# Sheet1.net
KiCad netlist of a schematic drawn in Altium Designer
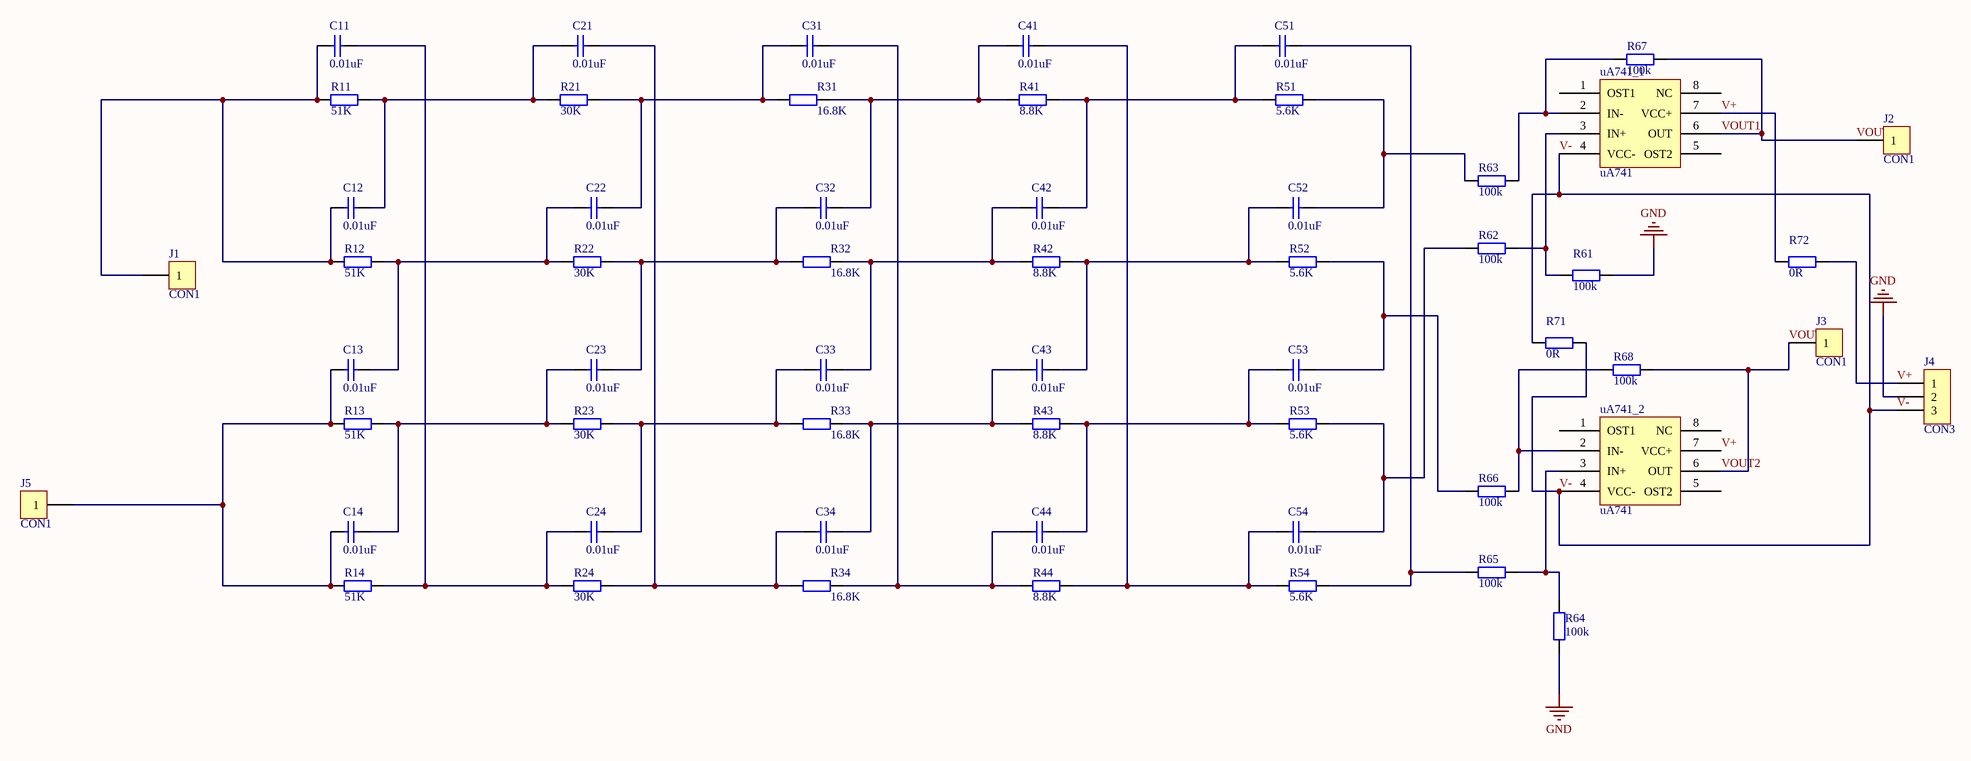
[diagram p0: Sheet1.SchDoc]

(export (version "E")
  (design (tool "Eeschema 10.0.6"))
  (components
    (comp (ref "C11")
      (value "0.01uF")
      (footprint "0603C")
      (description "Capacitor")
      (fields (field (name "PUBLISHER") "Altium Limited"))
      (libsource (lib "TH-SMT_WT_MP 1.0") (part "Cap"))
    )
    (comp (ref "C12")
      (value "0.01uF")
      (footprint "0603C")
      (description "Capacitor")
      (fields (field (name "PUBLISHER") "Altium Limited"))
      (libsource (lib "TH-SMT_WT_MP 1.0") (part "Cap"))
    )
    (comp (ref "C13")
      (value "0.01uF")
      (footprint "0603C")
      (description "Capacitor")
      (fields (field (name "PUBLISHER") "Altium Limited"))
      (libsource (lib "TH-SMT_WT_MP 1.0") (part "Cap"))
    )
    (comp (ref "C14")
      (value "0.01uF")
      (footprint "0603C")
      (description "Capacitor")
      (fields (field (name "PUBLISHER") "Altium Limited"))
      (libsource (lib "TH-SMT_WT_MP 1.0") (part "Cap"))
    )
    (comp (ref "C21")
      (value "0.01uF")
      (footprint "0603C")
      (description "Capacitor")
      (fields (field (name "PUBLISHER") "Altium Limited"))
      (libsource (lib "TH-SMT_WT_MP 1.0") (part "Cap"))
    )
    (comp (ref "C22")
      (value "0.01uF")
      (footprint "0603C")
      (description "Capacitor")
      (fields (field (name "PUBLISHER") "Altium Limited"))
      (libsource (lib "TH-SMT_WT_MP 1.0") (part "Cap"))
    )
    (comp (ref "C23")
      (value "0.01uF")
      (footprint "0603C")
      (description "Capacitor")
      (fields (field (name "PUBLISHER") "Altium Limited"))
      (libsource (lib "TH-SMT_WT_MP 1.0") (part "Cap"))
    )
    (comp (ref "C24")
      (value "0.01uF")
      (footprint "0603C")
      (description "Capacitor")
      (fields (field (name "PUBLISHER") "Altium Limited"))
      (libsource (lib "TH-SMT_WT_MP 1.0") (part "Cap"))
    )
    (comp (ref "C31")
      (value "0.01uF")
      (footprint "0603C")
      (description "Capacitor")
      (fields (field (name "PUBLISHER") "Altium Limited"))
      (libsource (lib "TH-SMT_WT_MP 1.0") (part "Cap"))
    )
    (comp (ref "C32")
      (value "0.01uF")
      (footprint "0603C")
      (description "Capacitor")
      (fields (field (name "PUBLISHER") "Altium Limited"))
      (libsource (lib "TH-SMT_WT_MP 1.0") (part "Cap"))
    )
    (comp (ref "C33")
      (value "0.01uF")
      (footprint "0603C")
      (description "Capacitor")
      (fields (field (name "PUBLISHER") "Altium Limited"))
      (libsource (lib "TH-SMT_WT_MP 1.0") (part "Cap"))
    )
    (comp (ref "C34")
      (value "0.01uF")
      (footprint "0603C")
      (description "Capacitor")
      (fields (field (name "PUBLISHER") "Altium Limited"))
      (libsource (lib "TH-SMT_WT_MP 1.0") (part "Cap"))
    )
    (comp (ref "C41")
      (value "0.01uF")
      (footprint "0603C")
      (description "Capacitor")
      (fields (field (name "PUBLISHER") "Altium Limited"))
      (libsource (lib "TH-SMT_WT_MP 1.0") (part "Cap"))
    )
    (comp (ref "C42")
      (value "0.01uF")
      (footprint "0603C")
      (description "Capacitor")
      (fields (field (name "PUBLISHER") "Altium Limited"))
      (libsource (lib "TH-SMT_WT_MP 1.0") (part "Cap"))
    )
    (comp (ref "C43")
      (value "0.01uF")
      (footprint "0603C")
      (description "Capacitor")
      (fields (field (name "PUBLISHER") "Altium Limited"))
      (libsource (lib "TH-SMT_WT_MP 1.0") (part "Cap"))
    )
    (comp (ref "C44")
      (value "0.01uF")
      (footprint "0603C")
      (description "Capacitor")
      (fields (field (name "PUBLISHER") "Altium Limited"))
      (libsource (lib "TH-SMT_WT_MP 1.0") (part "Cap"))
    )
    (comp (ref "C51")
      (value "0.01uF")
      (footprint "0603C")
      (description "Capacitor")
      (fields (field (name "PUBLISHER") "Altium Limited"))
      (libsource (lib "TH-SMT_WT_MP 1.0") (part "Cap"))
    )
    (comp (ref "C52")
      (value "0.01uF")
      (footprint "0603C")
      (description "Capacitor")
      (fields (field (name "PUBLISHER") "Altium Limited"))
      (libsource (lib "TH-SMT_WT_MP 1.0") (part "Cap"))
    )
    (comp (ref "C53")
      (value "0.01uF")
      (footprint "0603C")
      (description "Capacitor")
      (fields (field (name "PUBLISHER") "Altium Limited"))
      (libsource (lib "TH-SMT_WT_MP 1.0") (part "Cap"))
    )
    (comp (ref "C54")
      (value "0.01uF")
      (footprint "0603C")
      (description "Capacitor")
      (fields (field (name "PUBLISHER") "Altium Limited"))
      (libsource (lib "TH-SMT_WT_MP 1.0") (part "Cap"))
    )
    (comp (ref "J1") (value "CON1") (footprint "PIN-1-1.0") (libsource (lib "常用元件库") (part "CON1")))
    (comp (ref "J2") (value "CON1") (footprint "PIN-1-1.0") (libsource (lib "常用元件库") (part "CON1")))
    (comp (ref "J3") (value "CON1") (footprint "PIN-1-1.0") (libsource (lib "常用元件库") (part "CON1")))
    (comp (ref "J4") (value "CON3") (footprint "PIN-3-2.54-1.0") (libsource (lib "常用元件库") (part "CON3")))
    (comp (ref "J5") (value "CON1") (footprint "PIN-1-1.0") (libsource (lib "") (part "CON1_1")))
    (comp (ref "R11")
      (value "51K")
      (footprint "0603R")
      (description "Resistor")
      (fields (field (name "PUBLISHER") "Altium Limited"))
      (libsource (lib "") (part "Res2_1"))
    )
    (comp (ref "R12")
      (value "51K")
      (footprint "0603R")
      (description "Resistor")
      (fields (field (name "PUBLISHER") "Altium Limited"))
      (libsource (lib "") (part "Res2_1"))
    )
    (comp (ref "R13")
      (value "51K")
      (footprint "0603R")
      (description "Resistor")
      (fields (field (name "PUBLISHER") "Altium Limited"))
      (libsource (lib "") (part "Res2_1"))
    )
    (comp (ref "R14")
      (value "51K")
      (footprint "0603R")
      (description "Resistor")
      (fields (field (name "PUBLISHER") "Altium Limited"))
      (libsource (lib "") (part "Res2_1"))
    )
    (comp (ref "R21")
      (value "30K")
      (footprint "0603R")
      (description "Resistor")
      (fields (field (name "PUBLISHER") "Altium Limited"))
      (libsource (lib "") (part "Res2_1"))
    )
    (comp (ref "R22")
      (value "30K")
      (footprint "0603R")
      (description "Resistor")
      (fields (field (name "PUBLISHER") "Altium Limited"))
      (libsource (lib "") (part "Res2_1"))
    )
    (comp (ref "R23")
      (value "30K")
      (footprint "0603R")
      (description "Resistor")
      (fields (field (name "PUBLISHER") "Altium Limited"))
      (libsource (lib "") (part "Res2_1"))
    )
    (comp (ref "R24")
      (value "30K")
      (footprint "0603R")
      (description "Resistor")
      (fields (field (name "PUBLISHER") "Altium Limited"))
      (libsource (lib "") (part "Res2_1"))
    )
    (comp (ref "R31")
      (value "16.8K")
      (footprint "0603R")
      (description "Resistor")
      (fields (field (name "PUBLISHER") "Altium Limited"))
      (libsource (lib "") (part "Res2_1"))
    )
    (comp (ref "R32")
      (value "16.8K")
      (footprint "0603R")
      (description "Resistor")
      (fields (field (name "PUBLISHER") "Altium Limited"))
      (libsource (lib "") (part "Res2_1"))
    )
    (comp (ref "R33")
      (value "16.8K")
      (footprint "0603R")
      (description "Resistor")
      (fields (field (name "PUBLISHER") "Altium Limited"))
      (libsource (lib "") (part "Res2_1"))
    )
    (comp (ref "R34")
      (value "16.8K")
      (footprint "0603R")
      (description "Resistor")
      (fields (field (name "PUBLISHER") "Altium Limited"))
      (libsource (lib "") (part "Res2_1"))
    )
    (comp (ref "R41")
      (value "8.8K")
      (footprint "0603R")
      (description "Resistor")
      (fields (field (name "PUBLISHER") "Altium Limited"))
      (libsource (lib "") (part "Res2_1"))
    )
    (comp (ref "R42")
      (value "8.8K")
      (footprint "0603R")
      (description "Resistor")
      (fields (field (name "PUBLISHER") "Altium Limited"))
      (libsource (lib "") (part "Res2_1"))
    )
    (comp (ref "R43")
      (value "8.8K")
      (footprint "0603R")
      (description "Resistor")
      (fields (field (name "PUBLISHER") "Altium Limited"))
      (libsource (lib "") (part "Res2_1"))
    )
    (comp (ref "R44")
      (value "8.8K")
      (footprint "0603R")
      (description "Resistor")
      (fields (field (name "PUBLISHER") "Altium Limited"))
      (libsource (lib "") (part "Res2_1"))
    )
    (comp (ref "R51")
      (value "5.6K")
      (footprint "0603R")
      (description "Resistor")
      (fields (field (name "PUBLISHER") "Altium Limited"))
      (libsource (lib "TH-SMT_WT_MP 1.0") (part "Res2"))
    )
    (comp (ref "R52")
      (value "5.6K")
      (footprint "0603R")
      (description "Resistor")
      (fields (field (name "PUBLISHER") "Altium Limited"))
      (libsource (lib "TH-SMT_WT_MP 1.0") (part "Res2"))
    )
    (comp (ref "R53")
      (value "5.6K")
      (footprint "0603R")
      (description "Resistor")
      (fields (field (name "PUBLISHER") "Altium Limited"))
      (libsource (lib "TH-SMT_WT_MP 1.0") (part "Res2"))
    )
    (comp (ref "R54")
      (value "5.6K")
      (footprint "0603R")
      (description "Resistor")
      (fields (field (name "PUBLISHER") "Altium Limited"))
      (libsource (lib "TH-SMT_WT_MP 1.0") (part "Res2"))
    )
    (comp (ref "R61")
      (value "100k")
      (footprint "0603R")
      (description "Resistor")
      (libsource (lib "") (part "RES_1"))
    )
    (comp (ref "R62")
      (value "100k")
      (footprint "Inductor2")
      (description "Resistor")
      (libsource (lib "General") (part "RES"))
    )
    (comp (ref "R63")
      (value "100k")
      (footprint "0603R")
      (description "Resistor")
      (libsource (lib "General") (part "RES"))
    )
    (comp (ref "R64")
      (value "100k")
      (footprint "0603R")
      (description "Resistor")
      (libsource (lib "") (part "RES_2"))
    )
    (comp (ref "R65")
      (value "100k")
      (footprint "0603R")
      (description "Resistor")
      (libsource (lib "General") (part "RES"))
    )
    (comp (ref "R66")
      (value "100k")
      (footprint "Inductor2")
      (description "Resistor")
      (libsource (lib "General") (part "RES"))
    )
    (comp (ref "R67")
      (value "100k")
      (footprint "0603R")
      (description "Resistor")
      (libsource (lib "General") (part "RES"))
    )
    (comp (ref "R68")
      (value "100k")
      (footprint "0603R")
      (description "Resistor")
      (libsource (lib "General") (part "RES"))
    )
    (comp (ref "R71")
      (value "0R")
      (footprint "Inductor2")
      (description "Resistor")
      (libsource (lib "") (part "RES_1"))
    )
    (comp (ref "R72")
      (value "0R")
      (footprint "Inductor2")
      (description "Resistor")
      (libsource (lib "") (part "RES_1"))
    )
    (comp (ref "uA741_1") (value "uA741") (footprint "DIP-8") (libsource (lib "General") (part "uA741")))
    (comp (ref "uA741_2") (value "uA741") (footprint "DIP-8") (libsource (lib "General") (part "uA741")))
  )
  (nets
    (net (code "1") (name "/V+") (class "Default")
      (node (ref "J4") (pin "1") (pinfunction "1_1") (pintype "passive"))
      (node (ref "R72") (pin "1") (pinfunction "1_1") (pintype "passive"))
      (node (ref "R72") (pin "2") (pinfunction "2_2") (pintype "passive"))
      (node (ref "uA741_1") (pin "7") (pinfunction "VCC+_7") (pintype "passive"))
      (node (ref "uA741_2") (pin "7") (pinfunction "VCC+_7") (pintype "passive"))
    )
    (net (code "2") (name "/V-") (class "Default")
      (node (ref "J4") (pin "3") (pinfunction "3_3") (pintype "passive"))
      (node (ref "R71") (pin "1") (pinfunction "1_1") (pintype "passive"))
      (node (ref "R71") (pin "2") (pinfunction "2_2") (pintype "passive"))
      (node (ref "uA741_1") (pin "4") (pinfunction "VCC-_4") (pintype "passive"))
      (node (ref "uA741_2") (pin "4") (pinfunction "VCC-_4") (pintype "passive"))
    )
    (net (code "3") (name "/VOUT1") (class "Default")
      (node (ref "J2") (pin "1") (pinfunction "1_1") (pintype "passive"))
      (node (ref "R67") (pin "2") (pinfunction "2_2") (pintype "passive"))
      (node (ref "uA741_1") (pin "6") (pinfunction "OUT_6") (pintype "passive"))
    )
    (net (code "4") (name "/VOUT2") (class "Default")
      (node (ref "J3") (pin "1") (pinfunction "1_1") (pintype "passive"))
      (node (ref "R68") (pin "2") (pinfunction "2_2") (pintype "passive"))
      (node (ref "uA741_2") (pin "6") (pinfunction "OUT_6") (pintype "passive"))
    )
    (net (code "5") (name "GND") (class "Default")
      (node (ref "J4") (pin "2") (pinfunction "2_2") (pintype "passive"))
      (node (ref "R61") (pin "1") (pinfunction "1_1") (pintype "passive"))
      (node (ref "R64") (pin "2") (pinfunction "2_2") (pintype "passive"))
    )
    (net (code "6") (name "Net-(C11-Pad1)") (class "Default")
      (node (ref "C11") (pin "1") (pinfunction "1_1") (pintype "passive"))
      (node (ref "C12") (pin "1") (pinfunction "1_1") (pintype "passive"))
      (node (ref "J1") (pin "1") (pinfunction "1_1") (pintype "passive"))
      (node (ref "R11") (pin "1") (pinfunction "1_1") (pintype "passive"))
      (node (ref "R12") (pin "1") (pinfunction "1_1") (pintype "passive"))
    )
    (net (code "7") (name "Net-(C11-Pad2)") (class "Default")
      (node (ref "C11") (pin "2") (pinfunction "2_2") (pintype "passive"))
      (node (ref "C24") (pin "1") (pinfunction "1_1") (pintype "passive"))
      (node (ref "R14") (pin "2") (pinfunction "2_2") (pintype "passive"))
      (node (ref "R24") (pin "1") (pinfunction "1_1") (pintype "passive"))
    )
    (net (code "8") (name "Net-(C12-Pad2)") (class "Default")
      (node (ref "C12") (pin "2") (pinfunction "2_2") (pintype "passive"))
      (node (ref "C21") (pin "1") (pinfunction "1_1") (pintype "passive"))
      (node (ref "R11") (pin "2") (pinfunction "2_2") (pintype "passive"))
      (node (ref "R21") (pin "1") (pinfunction "1_1") (pintype "passive"))
    )
    (net (code "9") (name "Net-(C13-Pad1)") (class "Default")
      (node (ref "C13") (pin "1") (pinfunction "1_1") (pintype "passive"))
      (node (ref "C14") (pin "1") (pinfunction "1_1") (pintype "passive"))
      (node (ref "J5") (pin "1") (pinfunction "1_1") (pintype "passive"))
      (node (ref "R13") (pin "1") (pinfunction "1_1") (pintype "passive"))
      (node (ref "R14") (pin "1") (pinfunction "1_1") (pintype "passive"))
    )
    (net (code "10") (name "Net-(C13-Pad2)") (class "Default")
      (node (ref "C13") (pin "2") (pinfunction "2_2") (pintype "passive"))
      (node (ref "C22") (pin "1") (pinfunction "1_1") (pintype "passive"))
      (node (ref "R12") (pin "2") (pinfunction "2_2") (pintype "passive"))
      (node (ref "R22") (pin "1") (pinfunction "1_1") (pintype "passive"))
    )
    (net (code "11") (name "Net-(C14-Pad2)") (class "Default")
      (node (ref "C14") (pin "2") (pinfunction "2_2") (pintype "passive"))
      (node (ref "C23") (pin "1") (pinfunction "1_1") (pintype "passive"))
      (node (ref "R13") (pin "2") (pinfunction "2_2") (pintype "passive"))
      (node (ref "R23") (pin "1") (pinfunction "1_1") (pintype "passive"))
    )
    (net (code "12") (name "Net-(C21-Pad2)") (class "Default")
      (node (ref "C21") (pin "2") (pinfunction "2_2") (pintype "passive"))
      (node (ref "C34") (pin "1") (pinfunction "1_1") (pintype "passive"))
      (node (ref "R24") (pin "2") (pinfunction "2_2") (pintype "passive"))
      (node (ref "R34") (pin "1") (pinfunction "1_1") (pintype "passive"))
    )
    (net (code "13") (name "Net-(C22-Pad2)") (class "Default")
      (node (ref "C22") (pin "2") (pinfunction "2_2") (pintype "passive"))
      (node (ref "C31") (pin "1") (pinfunction "1_1") (pintype "passive"))
      (node (ref "R21") (pin "2") (pinfunction "2_2") (pintype "passive"))
      (node (ref "R31") (pin "1") (pinfunction "1_1") (pintype "passive"))
    )
    (net (code "14") (name "Net-(C23-Pad2)") (class "Default")
      (node (ref "C23") (pin "2") (pinfunction "2_2") (pintype "passive"))
      (node (ref "C32") (pin "1") (pinfunction "1_1") (pintype "passive"))
      (node (ref "R22") (pin "2") (pinfunction "2_2") (pintype "passive"))
      (node (ref "R32") (pin "1") (pinfunction "1_1") (pintype "passive"))
    )
    (net (code "15") (name "Net-(C24-Pad2)") (class "Default")
      (node (ref "C24") (pin "2") (pinfunction "2_2") (pintype "passive"))
      (node (ref "C33") (pin "1") (pinfunction "1_1") (pintype "passive"))
      (node (ref "R23") (pin "2") (pinfunction "2_2") (pintype "passive"))
      (node (ref "R33") (pin "1") (pinfunction "1_1") (pintype "passive"))
    )
    (net (code "16") (name "Net-(C31-Pad2)") (class "Default")
      (node (ref "C31") (pin "2") (pinfunction "2_2") (pintype "passive"))
      (node (ref "C44") (pin "1") (pinfunction "1_1") (pintype "passive"))
      (node (ref "R34") (pin "2") (pinfunction "2_2") (pintype "passive"))
      (node (ref "R44") (pin "1") (pinfunction "1_1") (pintype "passive"))
    )
    (net (code "17") (name "Net-(C32-Pad2)") (class "Default")
      (node (ref "C32") (pin "2") (pinfunction "2_2") (pintype "passive"))
      (node (ref "C41") (pin "1") (pinfunction "1_1") (pintype "passive"))
      (node (ref "R31") (pin "2") (pinfunction "2_2") (pintype "passive"))
      (node (ref "R41") (pin "1") (pinfunction "1_1") (pintype "passive"))
    )
    (net (code "18") (name "Net-(C33-Pad2)") (class "Default")
      (node (ref "C33") (pin "2") (pinfunction "2_2") (pintype "passive"))
      (node (ref "C42") (pin "1") (pinfunction "1_1") (pintype "passive"))
      (node (ref "R32") (pin "2") (pinfunction "2_2") (pintype "passive"))
      (node (ref "R42") (pin "1") (pinfunction "1_1") (pintype "passive"))
    )
    (net (code "19") (name "Net-(C34-Pad2)") (class "Default")
      (node (ref "C34") (pin "2") (pinfunction "2_2") (pintype "passive"))
      (node (ref "C43") (pin "1") (pinfunction "1_1") (pintype "passive"))
      (node (ref "R33") (pin "2") (pinfunction "2_2") (pintype "passive"))
      (node (ref "R43") (pin "1") (pinfunction "1_1") (pintype "passive"))
    )
    (net (code "20") (name "Net-(C41-Pad2)") (class "Default")
      (node (ref "C41") (pin "2") (pinfunction "2_2") (pintype "passive"))
      (node (ref "C54") (pin "1") (pinfunction "1_1") (pintype "passive"))
      (node (ref "R44") (pin "2") (pinfunction "2_2") (pintype "passive"))
      (node (ref "R54") (pin "2") (pinfunction "2_2") (pintype "passive"))
    )
    (net (code "21") (name "Net-(C42-Pad2)") (class "Default")
      (node (ref "C42") (pin "2") (pinfunction "2_2") (pintype "passive"))
      (node (ref "C51") (pin "1") (pinfunction "1_1") (pintype "passive"))
      (node (ref "R41") (pin "2") (pinfunction "2_2") (pintype "passive"))
      (node (ref "R51") (pin "2") (pinfunction "2_2") (pintype "passive"))
    )
    (net (code "22") (name "Net-(C43-Pad2)") (class "Default")
      (node (ref "C43") (pin "2") (pinfunction "2_2") (pintype "passive"))
      (node (ref "C52") (pin "1") (pinfunction "1_1") (pintype "passive"))
      (node (ref "R42") (pin "2") (pinfunction "2_2") (pintype "passive"))
      (node (ref "R52") (pin "2") (pinfunction "2_2") (pintype "passive"))
    )
    (net (code "23") (name "Net-(C44-Pad2)") (class "Default")
      (node (ref "C44") (pin "2") (pinfunction "2_2") (pintype "passive"))
      (node (ref "C53") (pin "1") (pinfunction "1_1") (pintype "passive"))
      (node (ref "R43") (pin "2") (pinfunction "2_2") (pintype "passive"))
      (node (ref "R53") (pin "2") (pinfunction "2_2") (pintype "passive"))
    )
    (net (code "24") (name "Net-(C51-Pad2)") (class "Default")
      (node (ref "C51") (pin "2") (pinfunction "2_2") (pintype "passive"))
      (node (ref "R54") (pin "1") (pinfunction "1_1") (pintype "passive"))
      (node (ref "R65") (pin "1") (pinfunction "1_1") (pintype "passive"))
    )
    (net (code "25") (name "Net-(C52-Pad2)") (class "Default")
      (node (ref "C52") (pin "2") (pinfunction "2_2") (pintype "passive"))
      (node (ref "R51") (pin "1") (pinfunction "1_1") (pintype "passive"))
      (node (ref "R63") (pin "1") (pinfunction "1_1") (pintype "passive"))
    )
    (net (code "26") (name "Net-(C53-Pad2)") (class "Default")
      (node (ref "C53") (pin "2") (pinfunction "2_2") (pintype "passive"))
      (node (ref "R52") (pin "1") (pinfunction "1_1") (pintype "passive"))
      (node (ref "R66") (pin "1") (pinfunction "1_1") (pintype "passive"))
    )
    (net (code "27") (name "Net-(C54-Pad2)") (class "Default")
      (node (ref "C54") (pin "2") (pinfunction "2_2") (pintype "passive"))
      (node (ref "R53") (pin "1") (pinfunction "1_1") (pintype "passive"))
      (node (ref "R62") (pin "1") (pinfunction "1_1") (pintype "passive"))
    )
    (net (code "28") (name "Net-(uA741_1-IN+)") (class "Default")
      (node (ref "R61") (pin "2") (pinfunction "2_2") (pintype "passive"))
      (node (ref "R62") (pin "2") (pinfunction "2_2") (pintype "passive"))
      (node (ref "uA741_1") (pin "3") (pinfunction "IN+_3") (pintype "passive"))
    )
    (net (code "29") (name "Net-(uA741_1-IN-)") (class "Default")
      (node (ref "R63") (pin "2") (pinfunction "2_2") (pintype "passive"))
      (node (ref "R67") (pin "1") (pinfunction "1_1") (pintype "passive"))
      (node (ref "uA741_1") (pin "2") (pinfunction "IN-_2") (pintype "passive"))
    )
    (net (code "30") (name "Net-(uA741_2-IN+)") (class "Default")
      (node (ref "R64") (pin "1") (pinfunction "1_1") (pintype "passive"))
      (node (ref "R65") (pin "2") (pinfunction "2_2") (pintype "passive"))
      (node (ref "uA741_2") (pin "3") (pinfunction "IN+_3") (pintype "passive"))
    )
    (net (code "31") (name "Net-(uA741_2-IN-)") (class "Default")
      (node (ref "R66") (pin "2") (pinfunction "2_2") (pintype "passive"))
      (node (ref "R68") (pin "1") (pinfunction "1_1") (pintype "passive"))
      (node (ref "uA741_2") (pin "2") (pinfunction "IN-_2") (pintype "passive"))
    )
    (net (code "32") (name "unconnected-(uA741_1-NC-Pad8)") (class "Default")
      (node (ref "uA741_1") (pin "8") (pinfunction "NC_8") (pintype "passive"))
    )
    (net (code "33") (name "unconnected-(uA741_1-OST1-Pad1)") (class "Default")
      (node (ref "uA741_1") (pin "1") (pinfunction "OST1_1") (pintype "passive"))
    )
    (net (code "34") (name "unconnected-(uA741_1-OST2-Pad5)") (class "Default")
      (node (ref "uA741_1") (pin "5") (pinfunction "OST2_5") (pintype "passive"))
    )
    (net (code "35") (name "unconnected-(uA741_2-NC-Pad8)") (class "Default")
      (node (ref "uA741_2") (pin "8") (pinfunction "NC_8") (pintype "passive"))
    )
    (net (code "36") (name "unconnected-(uA741_2-OST1-Pad1)") (class "Default")
      (node (ref "uA741_2") (pin "1") (pinfunction "OST1_1") (pintype "passive"))
    )
    (net (code "37") (name "unconnected-(uA741_2-OST2-Pad5)") (class "Default")
      (node (ref "uA741_2") (pin "5") (pinfunction "OST2_5") (pintype "passive"))
    )
  )
)
